# AMS1117-3_3.net
KiCad netlist of a schematic drawn in Altium Designer
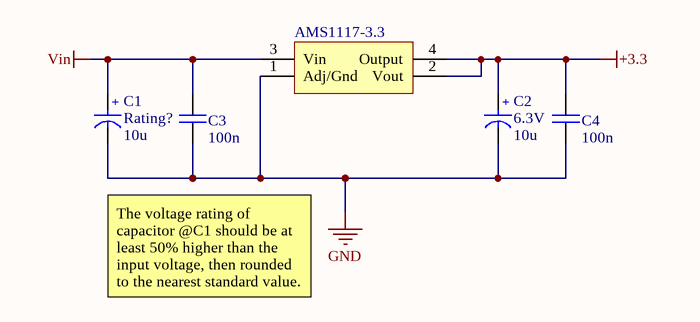
[diagram p0: AMS1117-3.3.SchDoc]

(export (version "E")
  (design (tool "Eeschema 10.0.6"))
  (components
    (comp (ref "AMS1117-3.3")
      (value "3.3V")
      (footprint "SOT223_M")
      (description "1'A Positive voltage regulator")
      (fields (field (name "VALIDATION") "Valid"))
      (libsource (lib "aKaReZa") (part "IC_Reg_AMS1117_3.3"))
    )
    (comp (ref "C1")
      (value "10u")
      (footprint "SMT_C_Tantalum_B")
      (description "Tantalum Capacitor,TAJ Series-SMD")
      (fields (field (name "RATING") "Rating?") (field (name "VALIDATION") "Valid"))
      (libsource (lib "aKaReZa") (part "Cap_Tantalum"))
    )
    (comp (ref "C2")
      (value "10u")
      (footprint "SMT_C_Tantalum_B")
      (description "Tantalum Capacitor,TAJ Series-SMD")
      (fields (field (name "RATING") "6.3V") (field (name "VALIDATION") "Valid"))
      (libsource (lib "aKaReZa") (part "Cap_Tantalum"))
    )
    (comp (ref "C3")
      (value "100n")
      (footprint "CAP 0805/2012")
      (description "Bipolar ceramic capacitor SMD")
      (fields (field (name "VALIDATION") "Valid"))
      (libsource (lib "aKaReZa") (part "Cap_Multi_SMD_100nF_0805"))
    )
    (comp (ref "C4")
      (value "100n")
      (footprint "CAP 0805/2012")
      (description "Bipolar ceramic capacitor SMD")
      (fields (field (name "VALIDATION") "Valid"))
      (libsource (lib "aKaReZa") (part "Cap_Multi_SMD_100nF_0805"))
    )
  )
  (nets
    (net (code "1") (name "+3.3") (class "Default")
      (node (ref "AMS1117-3.3") (pin "2") (pinfunction "Vout_2") (pintype "passive"))
      (node (ref "AMS1117-3.3") (pin "4") (pinfunction "Output_4") (pintype "passive"))
      (node (ref "C2") (pin "1") (pinfunction "+_1") (pintype "passive"))
      (node (ref "C4") (pin "1") (pinfunction "1_1") (pintype "passive"))
    )
    (net (code "2") (name "GND") (class "Default")
      (node (ref "AMS1117-3.3") (pin "1") (pinfunction "Adj/Gnd_1") (pintype "passive"))
      (node (ref "C1") (pin "2") (pinfunction "-_2") (pintype "passive"))
      (node (ref "C2") (pin "2") (pinfunction "-_2") (pintype "passive"))
      (node (ref "C3") (pin "2") (pinfunction "2_2") (pintype "passive"))
      (node (ref "C4") (pin "2") (pinfunction "2_2") (pintype "passive"))
    )
    (net (code "3") (name "Vin") (class "Default")
      (node (ref "AMS1117-3.3") (pin "3") (pinfunction "Vin_3") (pintype "passive"))
      (node (ref "C1") (pin "1") (pinfunction "+_1") (pintype "passive"))
      (node (ref "C3") (pin "1") (pinfunction "1_1") (pintype "passive"))
    )
  )
)
